# WeatherStation.net
KiCad netlist of a schematic drawn in Altium Designer
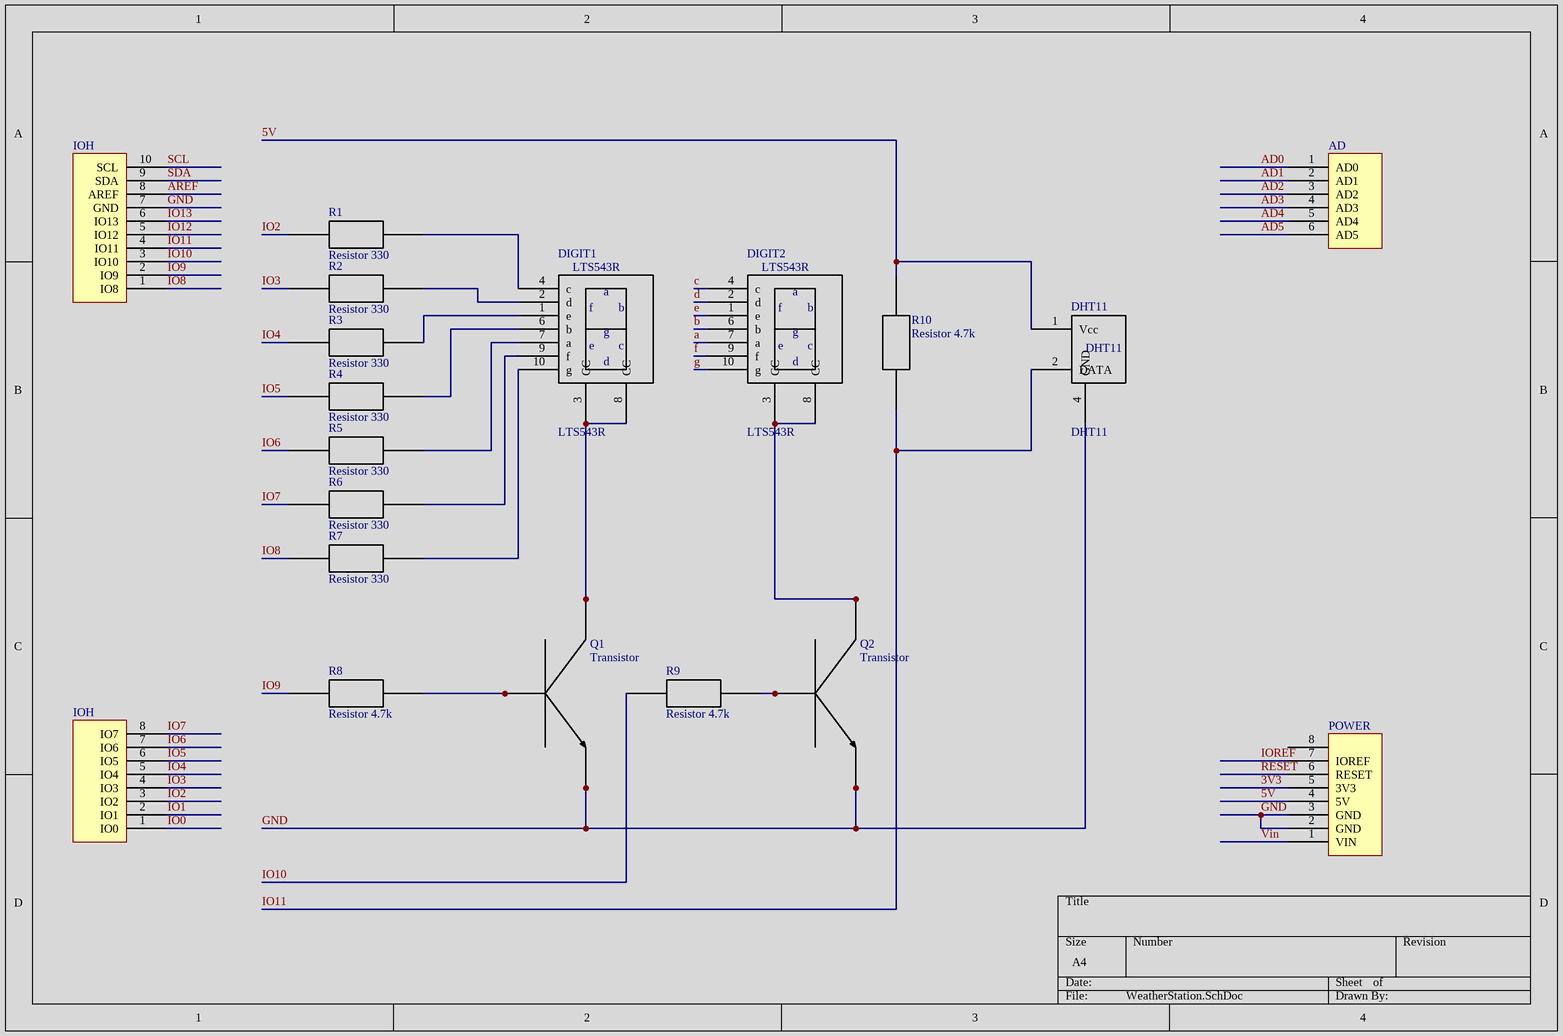
[diagram p0: WeatherStation.SchDoc]

(export (version "E")
  (design (tool "Eeschema 10.0.6"))
  (components
    (comp (ref "AD") (value "AD") (footprint "AD") (libsource (lib "Schlib1") (part "AD")))
    (comp (ref "DHT11") (value "DHT11") (footprint "DHT11") (libsource (lib "WeatherStation") (part "DHT11")))
    (comp (ref "DIGIT1")
      (value "LTS543R")
      (footprint "7SEGMENT")
      (libsource (lib "WeatherStation") (part "LTS543R"))
    )
    (comp (ref "DIGIT2")
      (value "LTS543R")
      (footprint "7SEGMENT")
      (libsource (lib "WeatherStation") (part "LTS543R"))
    )
    (comp (ref "IOH 1") (value "IOH 1") (footprint "IOH 1") (libsource (lib "Schlib1") (part "IOH 1")))
    (comp (ref "IOH 2") (value "IOH 2") (footprint "IOH 2") (libsource (lib "Schlib1") (part "IOH 2")))
    (comp (ref "POWER") (value "POWER") (footprint "POWER") (libsource (lib "Schlib1") (part "POWER")))
    (comp (ref "Q1")
      (value "Transistor")
      (footprint "TRANSISTOR")
      (libsource (lib "WeatherStation") (part "Transistor"))
    )
    (comp (ref "Q2")
      (value "Transistor")
      (footprint "TRANSISTOR")
      (libsource (lib "WeatherStation") (part "Transistor"))
    )
    (comp (ref "R1")
      (value "Resistor 330")
      (footprint "RESISTOR")
      (libsource (lib "WeatherStation") (part "Resistor 330"))
    )
    (comp (ref "R2")
      (value "Resistor 330")
      (footprint "RESISTOR")
      (libsource (lib "WeatherStation") (part "Resistor 330"))
    )
    (comp (ref "R3")
      (value "Resistor 330")
      (footprint "RESISTOR")
      (libsource (lib "WeatherStation") (part "Resistor 330"))
    )
    (comp (ref "R4")
      (value "Resistor 330")
      (footprint "RESISTOR")
      (libsource (lib "WeatherStation") (part "Resistor 330"))
    )
    (comp (ref "R5")
      (value "Resistor 330")
      (footprint "RESISTOR")
      (libsource (lib "WeatherStation") (part "Resistor 330"))
    )
    (comp (ref "R6")
      (value "Resistor 330")
      (footprint "RESISTOR")
      (libsource (lib "WeatherStation") (part "Resistor 330"))
    )
    (comp (ref "R7")
      (value "Resistor 330")
      (footprint "RESISTOR")
      (libsource (lib "WeatherStation") (part "Resistor 330"))
    )
    (comp (ref "R8")
      (value "Resistor 4.7k")
      (footprint "RESISTOR")
      (libsource (lib "WeatherStation") (part "Resistor 4.7k"))
    )
    (comp (ref "R9")
      (value "Resistor 4.7k")
      (footprint "RESISTOR")
      (libsource (lib "WeatherStation") (part "Resistor 4.7k"))
    )
    (comp (ref "R10")
      (value "Resistor 4.7k")
      (footprint "RESISTOR")
      (libsource (lib "WeatherStation") (part "Resistor 4.7k"))
    )
  )
  (nets
    (net (code "1") (name "/3V3") (class "Default")
      (node (ref "POWER") (pin "5") (pinfunction "3V3_5") (pintype "passive"))
    )
    (net (code "2") (name "/5V") (class "Default")
      (node (ref "DHT11") (pin "1") (pinfunction "Vcc_1") (pintype "passive"))
      (node (ref "POWER") (pin "4") (pinfunction "5V_4") (pintype "passive"))
      (node (ref "R10") (pin "2") (pinfunction "2_2") (pintype "passive"))
    )
    (net (code "3") (name "/AD0") (class "Default")
      (node (ref "AD") (pin "1") (pinfunction "AD0_1") (pintype "passive"))
    )
    (net (code "4") (name "/AD1") (class "Default")
      (node (ref "AD") (pin "2") (pinfunction "AD1_2") (pintype "passive"))
    )
    (net (code "5") (name "/AD2") (class "Default")
      (node (ref "AD") (pin "3") (pinfunction "AD2_3") (pintype "passive"))
    )
    (net (code "6") (name "/AD3") (class "Default")
      (node (ref "AD") (pin "4") (pinfunction "AD3_4") (pintype "passive"))
    )
    (net (code "7") (name "/AD4") (class "Default")
      (node (ref "AD") (pin "5") (pinfunction "AD4_5") (pintype "passive"))
    )
    (net (code "8") (name "/AD5") (class "Default")
      (node (ref "AD") (pin "6") (pinfunction "AD5_6") (pintype "passive"))
    )
    (net (code "9") (name "/AREF") (class "Default")
      (node (ref "IOH 1") (pin "8") (pinfunction "AREF_8") (pintype "passive"))
    )
    (net (code "10") (name "/GND") (class "Default")
      (node (ref "DHT11") (pin "4") (pinfunction "GND_4") (pintype "passive"))
      (node (ref "IOH 1") (pin "7") (pinfunction "GND_7") (pintype "passive"))
      (node (ref "POWER") (pin "2") (pinfunction "GND_2") (pintype "passive"))
      (node (ref "POWER") (pin "3") (pinfunction "GND_3") (pintype "passive"))
      (node (ref "Q1") (pin "5") (pinfunction "5_5") (pintype "passive"))
      (node (ref "Q2") (pin "5") (pinfunction "5_5") (pintype "passive"))
    )
    (net (code "11") (name "/IO0") (class "Default")
      (node (ref "IOH 2") (pin "1") (pinfunction "IO0_1") (pintype "passive"))
    )
    (net (code "12") (name "/IO1") (class "Default")
      (node (ref "IOH 2") (pin "2") (pinfunction "IO1_2") (pintype "passive"))
    )
    (net (code "13") (name "/IO2") (class "Default")
      (node (ref "IOH 2") (pin "3") (pinfunction "IO2_3") (pintype "passive"))
      (node (ref "R1") (pin "1") (pinfunction "1_1") (pintype "passive"))
    )
    (net (code "14") (name "/IO3") (class "Default")
      (node (ref "IOH 2") (pin "4") (pinfunction "IO3_4") (pintype "passive"))
      (node (ref "R2") (pin "1") (pinfunction "1_1") (pintype "passive"))
    )
    (net (code "15") (name "/IO4") (class "Default")
      (node (ref "IOH 2") (pin "5") (pinfunction "IO4_5") (pintype "passive"))
      (node (ref "R3") (pin "1") (pinfunction "1_1") (pintype "passive"))
    )
    (net (code "16") (name "/IO5") (class "Default")
      (node (ref "IOH 2") (pin "6") (pinfunction "IO5_6") (pintype "passive"))
      (node (ref "R4") (pin "1") (pinfunction "1_1") (pintype "passive"))
    )
    (net (code "17") (name "/IO6") (class "Default")
      (node (ref "IOH 2") (pin "7") (pinfunction "IO6_7") (pintype "passive"))
      (node (ref "R5") (pin "1") (pinfunction "1_1") (pintype "passive"))
    )
    (net (code "18") (name "/IO7") (class "Default")
      (node (ref "IOH 2") (pin "8") (pinfunction "IO7_8") (pintype "passive"))
      (node (ref "R6") (pin "1") (pinfunction "1_1") (pintype "passive"))
    )
    (net (code "19") (name "/IO8") (class "Default")
      (node (ref "IOH 1") (pin "1") (pinfunction "IO8_1") (pintype "passive"))
      (node (ref "R7") (pin "1") (pinfunction "1_1") (pintype "passive"))
    )
    (net (code "20") (name "/IO9") (class "Default")
      (node (ref "IOH 1") (pin "2") (pinfunction "IO9_2") (pintype "passive"))
      (node (ref "R8") (pin "1") (pinfunction "1_1") (pintype "passive"))
    )
    (net (code "21") (name "/IO10") (class "Default")
      (node (ref "IOH 1") (pin "3") (pinfunction "IO10_3") (pintype "passive"))
      (node (ref "R9") (pin "1") (pinfunction "1_1") (pintype "passive"))
    )
    (net (code "22") (name "/IO11") (class "Default")
      (node (ref "DHT11") (pin "2") (pinfunction "DATA_2") (pintype "passive"))
      (node (ref "IOH 1") (pin "4") (pinfunction "IO11_4") (pintype "passive"))
      (node (ref "R10") (pin "1") (pinfunction "1_1") (pintype "passive"))
    )
    (net (code "23") (name "/IO12") (class "Default")
      (node (ref "IOH 1") (pin "5") (pinfunction "IO12_5") (pintype "passive"))
    )
    (net (code "24") (name "/IO13") (class "Default")
      (node (ref "IOH 1") (pin "6") (pinfunction "IO13_6") (pintype "passive"))
    )
    (net (code "25") (name "/IOREF") (class "Default")
      (node (ref "POWER") (pin "7") (pinfunction "IOREF_7") (pintype "passive"))
    )
    (net (code "26") (name "/RESET") (class "Default")
      (node (ref "POWER") (pin "6") (pinfunction "RESET_6") (pintype "passive"))
    )
    (net (code "27") (name "/SCL") (class "Default")
      (node (ref "IOH 1") (pin "10") (pinfunction "SCL_10") (pintype "passive"))
    )
    (net (code "28") (name "/SDA") (class "Default")
      (node (ref "IOH 1") (pin "9") (pinfunction "SDA_9") (pintype "passive"))
    )
    (net (code "29") (name "/Vin") (class "Default")
      (node (ref "POWER") (pin "1") (pinfunction "VIN_1") (pintype "passive"))
    )
    (net (code "30") (name "/a") (class "Default")
      (node (ref "DIGIT2") (pin "7") (pinfunction "a_7") (pintype "passive"))
    )
    (net (code "31") (name "/b") (class "Default")
      (node (ref "DIGIT2") (pin "6") (pinfunction "b_6") (pintype "passive"))
    )
    (net (code "32") (name "/c") (class "Default")
      (node (ref "DIGIT2") (pin "4") (pinfunction "c_4") (pintype "passive"))
    )
    (net (code "33") (name "/d") (class "Default")
      (node (ref "DIGIT2") (pin "2") (pinfunction "d_2") (pintype "passive"))
    )
    (net (code "34") (name "/e") (class "Default")
      (node (ref "DIGIT2") (pin "1") (pinfunction "e_1") (pintype "passive"))
    )
    (net (code "35") (name "/f") (class "Default")
      (node (ref "DIGIT2") (pin "9") (pinfunction "f_9") (pintype "passive"))
    )
    (net (code "36") (name "/g") (class "Default")
      (node (ref "DIGIT2") (pin "10") (pinfunction "g_10") (pintype "passive"))
    )
    (net (code "37") (name "Net-(DIGIT1-CC-Pad3)") (class "Default")
      (node (ref "DIGIT1") (pin "3") (pinfunction "CC_3") (pintype "passive"))
      (node (ref "DIGIT1") (pin "8") (pinfunction "CC_8") (pintype "passive"))
      (node (ref "Q1") (pin "7") (pinfunction "7_7") (pintype "passive"))
    )
    (net (code "38") (name "Net-(DIGIT1-a)") (class "Default")
      (node (ref "DIGIT1") (pin "7") (pinfunction "a_7") (pintype "passive"))
      (node (ref "R5") (pin "2") (pinfunction "2_2") (pintype "passive"))
    )
    (net (code "39") (name "Net-(DIGIT1-b)") (class "Default")
      (node (ref "DIGIT1") (pin "6") (pinfunction "b_6") (pintype "passive"))
      (node (ref "R4") (pin "2") (pinfunction "2_2") (pintype "passive"))
    )
    (net (code "40") (name "Net-(DIGIT1-c)") (class "Default")
      (node (ref "DIGIT1") (pin "4") (pinfunction "c_4") (pintype "passive"))
      (node (ref "R1") (pin "2") (pinfunction "2_2") (pintype "passive"))
    )
    (net (code "41") (name "Net-(DIGIT1-d)") (class "Default")
      (node (ref "DIGIT1") (pin "2") (pinfunction "d_2") (pintype "passive"))
      (node (ref "R2") (pin "2") (pinfunction "2_2") (pintype "passive"))
    )
    (net (code "42") (name "Net-(DIGIT1-e)") (class "Default")
      (node (ref "DIGIT1") (pin "1") (pinfunction "e_1") (pintype "passive"))
      (node (ref "R3") (pin "2") (pinfunction "2_2") (pintype "passive"))
    )
    (net (code "43") (name "Net-(DIGIT1-f)") (class "Default")
      (node (ref "DIGIT1") (pin "9") (pinfunction "f_9") (pintype "passive"))
      (node (ref "R6") (pin "2") (pinfunction "2_2") (pintype "passive"))
    )
    (net (code "44") (name "Net-(DIGIT1-g)") (class "Default")
      (node (ref "DIGIT1") (pin "10") (pinfunction "g_10") (pintype "passive"))
      (node (ref "R7") (pin "2") (pinfunction "2_2") (pintype "passive"))
    )
    (net (code "45") (name "Net-(DIGIT2-CC-Pad3)") (class "Default")
      (node (ref "DIGIT2") (pin "3") (pinfunction "CC_3") (pintype "passive"))
      (node (ref "DIGIT2") (pin "8") (pinfunction "CC_8") (pintype "passive"))
      (node (ref "Q2") (pin "7") (pinfunction "7_7") (pintype "passive"))
    )
    (net (code "46") (name "Net-(Q1-Pad6)") (class "Default")
      (node (ref "Q1") (pin "6") (pinfunction "6_6") (pintype "passive"))
      (node (ref "R8") (pin "2") (pinfunction "2_2") (pintype "passive"))
    )
    (net (code "47") (name "Net-(Q2-Pad6)") (class "Default")
      (node (ref "Q2") (pin "6") (pinfunction "6_6") (pintype "passive"))
      (node (ref "R9") (pin "2") (pinfunction "2_2") (pintype "passive"))
    )
    (net (code "48") (name "unconnected-(POWER-Pad8)") (class "Default")
      (node (ref "POWER") (pin "8") (pintype "passive"))
    )
  )
)
